# 4_SENSOR.net
KiCad netlist of a schematic drawn in Altium Designer
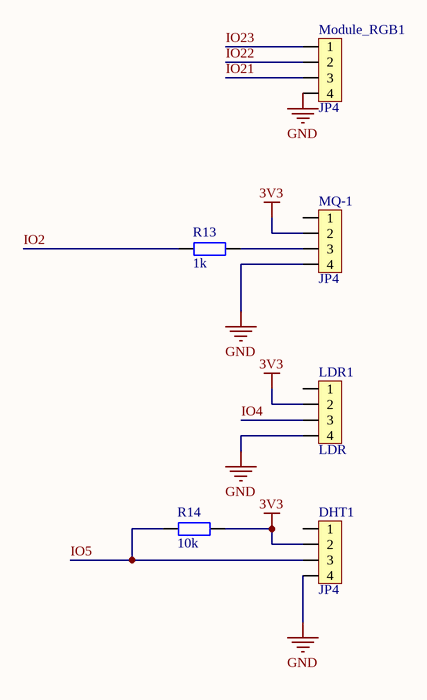
[diagram p0: 4.SENSOR.SchDoc]

(export (version "E")
  (design (tool "Eeschema 10.0.6"))
  (components
    (comp (ref "DHT1")
      (value "JP4")
      (footprint "JP4-C1T")
      (description "WR-PHD 2.54 mm Angled Socket Header")
      (fields
        (field (name "MANUFACTURER") "Würth Elektronik eiSos GmbH")
        (field (name "PARTNO") "613004143121")
        (field (name "CREATED BY") "Karrer Zheng")
      )
      (libsource (lib "Main") (part "JP4"))
    )
    (comp (ref "LDR1")
      (value "LDR")
      (footprint "JP4-C1T")
      (description "WR-PHD 2.54 mm Angled Socket Header")
      (fields
        (field (name "MANUFACTURER") "Würth Elektronik eiSos GmbH")
        (field (name "PARTNO") "613004143121")
        (field (name "CREATED BY") "Karrer Zheng")
      )
      (libsource (lib "Main") (part "JP4"))
    )
    (comp (ref "Module_RGB1")
      (value "JP4")
      (footprint "JP4-C1T")
      (description "WR-PHD 2.54 mm Angled Socket Header")
      (fields
        (field (name "MANUFACTURER") "Würth Elektronik eiSos GmbH")
        (field (name "PARTNO") "613004143121")
        (field (name "CREATED BY") "Karrer Zheng")
      )
      (libsource (lib "Main") (part "JP4"))
    )
    (comp (ref "MQ-1")
      (value "JP4")
      (footprint "JP4-C1T")
      (description "WR-PHD 2.54 mm Angled Socket Header")
      (fields
        (field (name "MANUFACTURER") "Würth Elektronik eiSos GmbH")
        (field (name "PARTNO") "613004143121")
        (field (name "CREATED BY") "Karrer Zheng")
      )
      (libsource (lib "Main") (part "JP4"))
    )
    (comp (ref "R13")
      (value "1k")
      (footprint "RES-SMD-0805")
      (fields
        (field (name "MANUFACTURER") "Generic Components")
        (field (name "PUBLISHER") "Altium Hobart Technology Centre")
      )
      (libsource (lib "Main") (part "Resistor - SMD"))
    )
    (comp (ref "R14")
      (value "10k")
      (footprint "RES-SMD-0805")
      (description "1k")
      (fields
        (field (name "MANUFACTURER") "Generic Components")
        (field (name "PUBLISHER") "Altium Hobart Technology Centre")
      )
      (libsource (lib "Main") (part "Resistor - SMD"))
    )
  )
  (nets
    (net (code "1") (name "/IO2") (class "Default")
      (node (ref "R13") (pin "2") (pinfunction "2_2") (pintype "passive"))
    )
    (net (code "2") (name "/IO4") (class "Default")
      (node (ref "LDR1") (pin "3") (pinfunction "3_3") (pintype "passive"))
    )
    (net (code "3") (name "/IO5") (class "Default")
      (node (ref "DHT1") (pin "3") (pinfunction "3_3") (pintype "passive"))
      (node (ref "R14") (pin "2") (pinfunction "2_2") (pintype "passive"))
    )
    (net (code "4") (name "/IO21") (class "Default")
      (node (ref "Module_RGB1") (pin "3") (pinfunction "3_3") (pintype "passive"))
    )
    (net (code "5") (name "/IO22") (class "Default")
      (node (ref "Module_RGB1") (pin "2") (pinfunction "2_2") (pintype "passive"))
    )
    (net (code "6") (name "/IO23") (class "Default")
      (node (ref "Module_RGB1") (pin "1") (pinfunction "1_1") (pintype "passive"))
    )
    (net (code "7") (name "3V3") (class "Default")
      (node (ref "DHT1") (pin "2") (pinfunction "2_2") (pintype "passive"))
      (node (ref "LDR1") (pin "2") (pinfunction "2_2") (pintype "passive"))
      (node (ref "MQ-1") (pin "2") (pinfunction "2_2") (pintype "passive"))
      (node (ref "R14") (pin "1") (pinfunction "1_1") (pintype "passive"))
    )
    (net (code "8") (name "GND") (class "Default")
      (node (ref "DHT1") (pin "4") (pinfunction "4_4") (pintype "passive"))
      (node (ref "LDR1") (pin "4") (pinfunction "4_4") (pintype "passive"))
      (node (ref "MQ-1") (pin "4") (pinfunction "4_4") (pintype "passive"))
      (node (ref "Module_RGB1") (pin "4") (pinfunction "4_4") (pintype "passive"))
    )
    (net (code "9") (name "Net-(MQ-1-Pad3)") (class "Default")
      (node (ref "MQ-1") (pin "3") (pinfunction "3_3") (pintype "passive"))
      (node (ref "R13") (pin "1") (pinfunction "1_1") (pintype "passive"))
    )
    (net (code "10") (name "unconnected-(DHT1-Pad1)") (class "Default")
      (node (ref "DHT1") (pin "1") (pinfunction "1_1") (pintype "passive"))
    )
    (net (code "11") (name "unconnected-(LDR1-Pad1)") (class "Default")
      (node (ref "LDR1") (pin "1") (pinfunction "1_1") (pintype "passive"))
    )
    (net (code "12") (name "unconnected-(MQ-1-Pad1)") (class "Default")
      (node (ref "MQ-1") (pin "1") (pinfunction "1_1") (pintype "passive"))
    )
  )
)
